# PicoBOB_DLX.net
KiCad netlist of a schematic drawn in Altium Designer
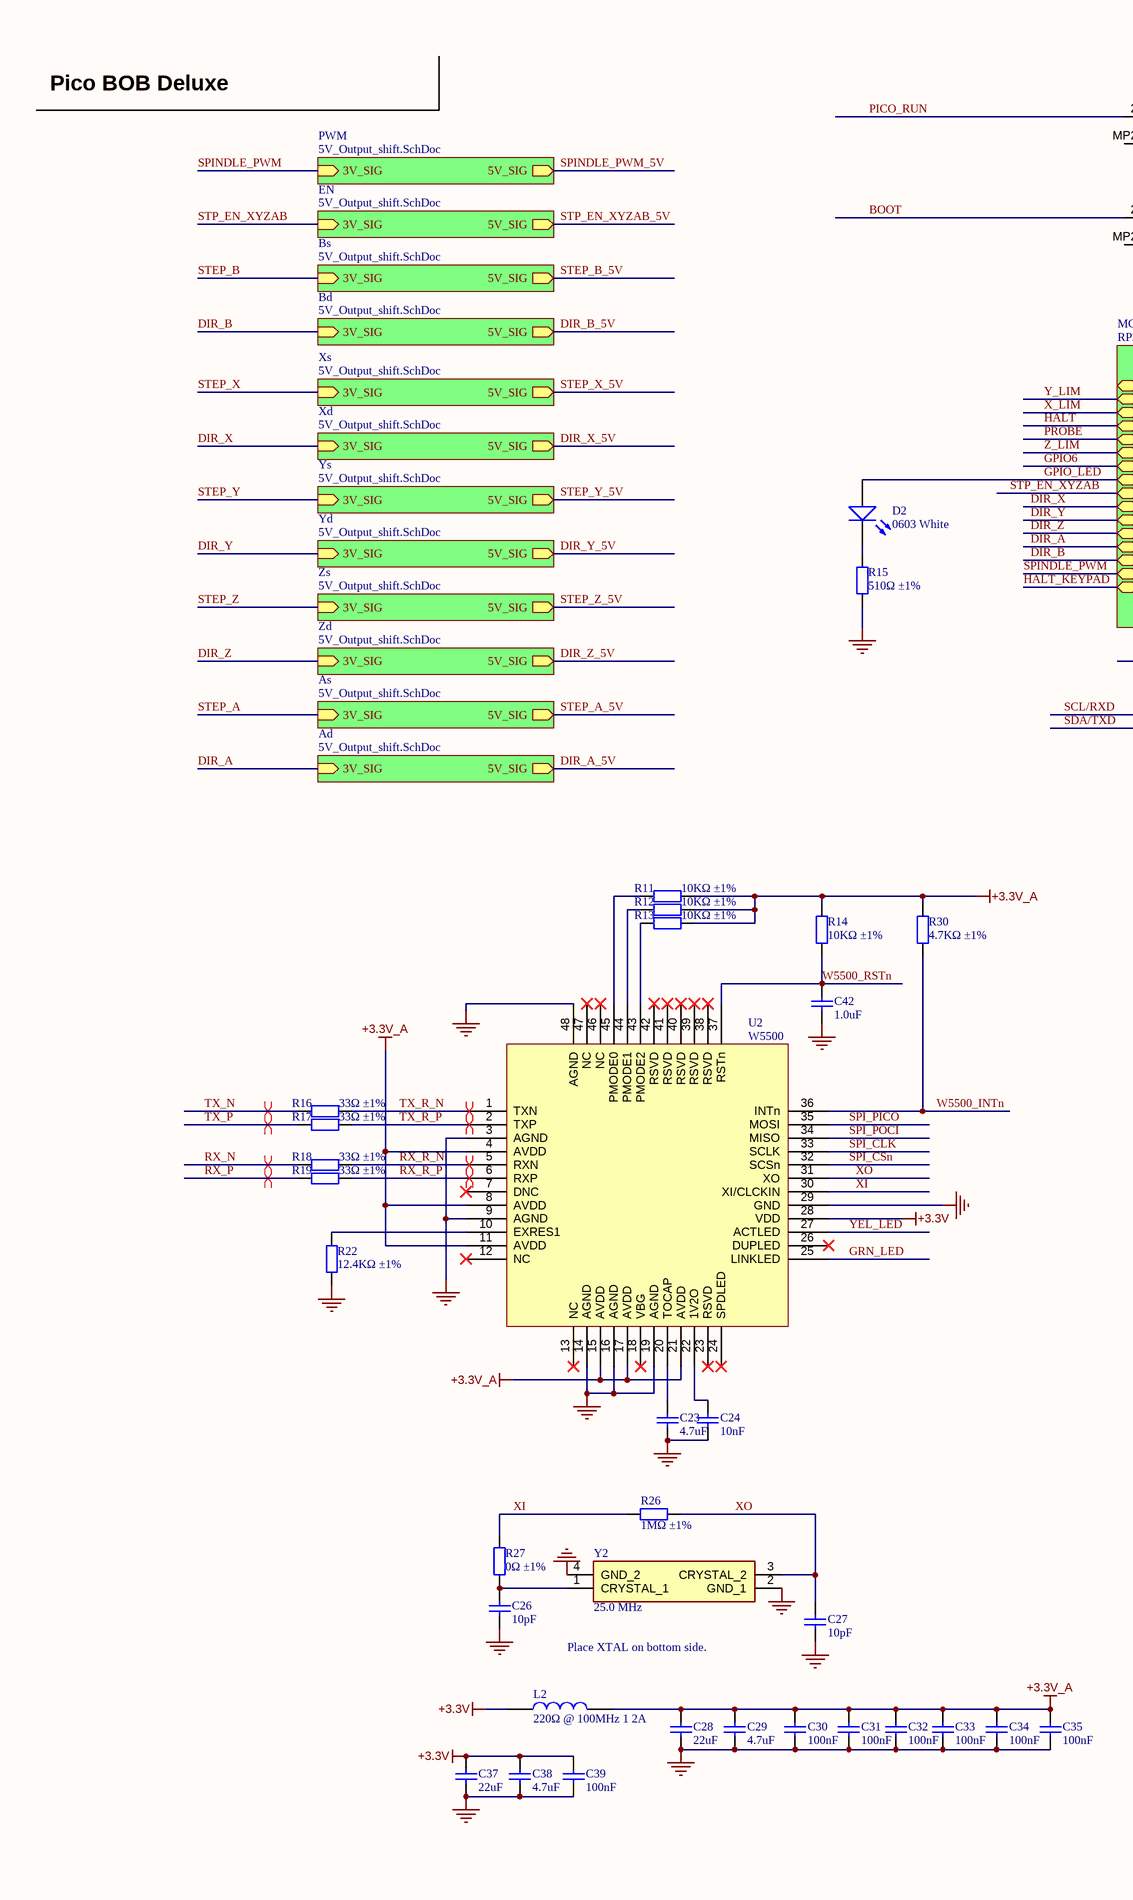
[diagram p0: PicoBOB_DLX.SchDoc, left]
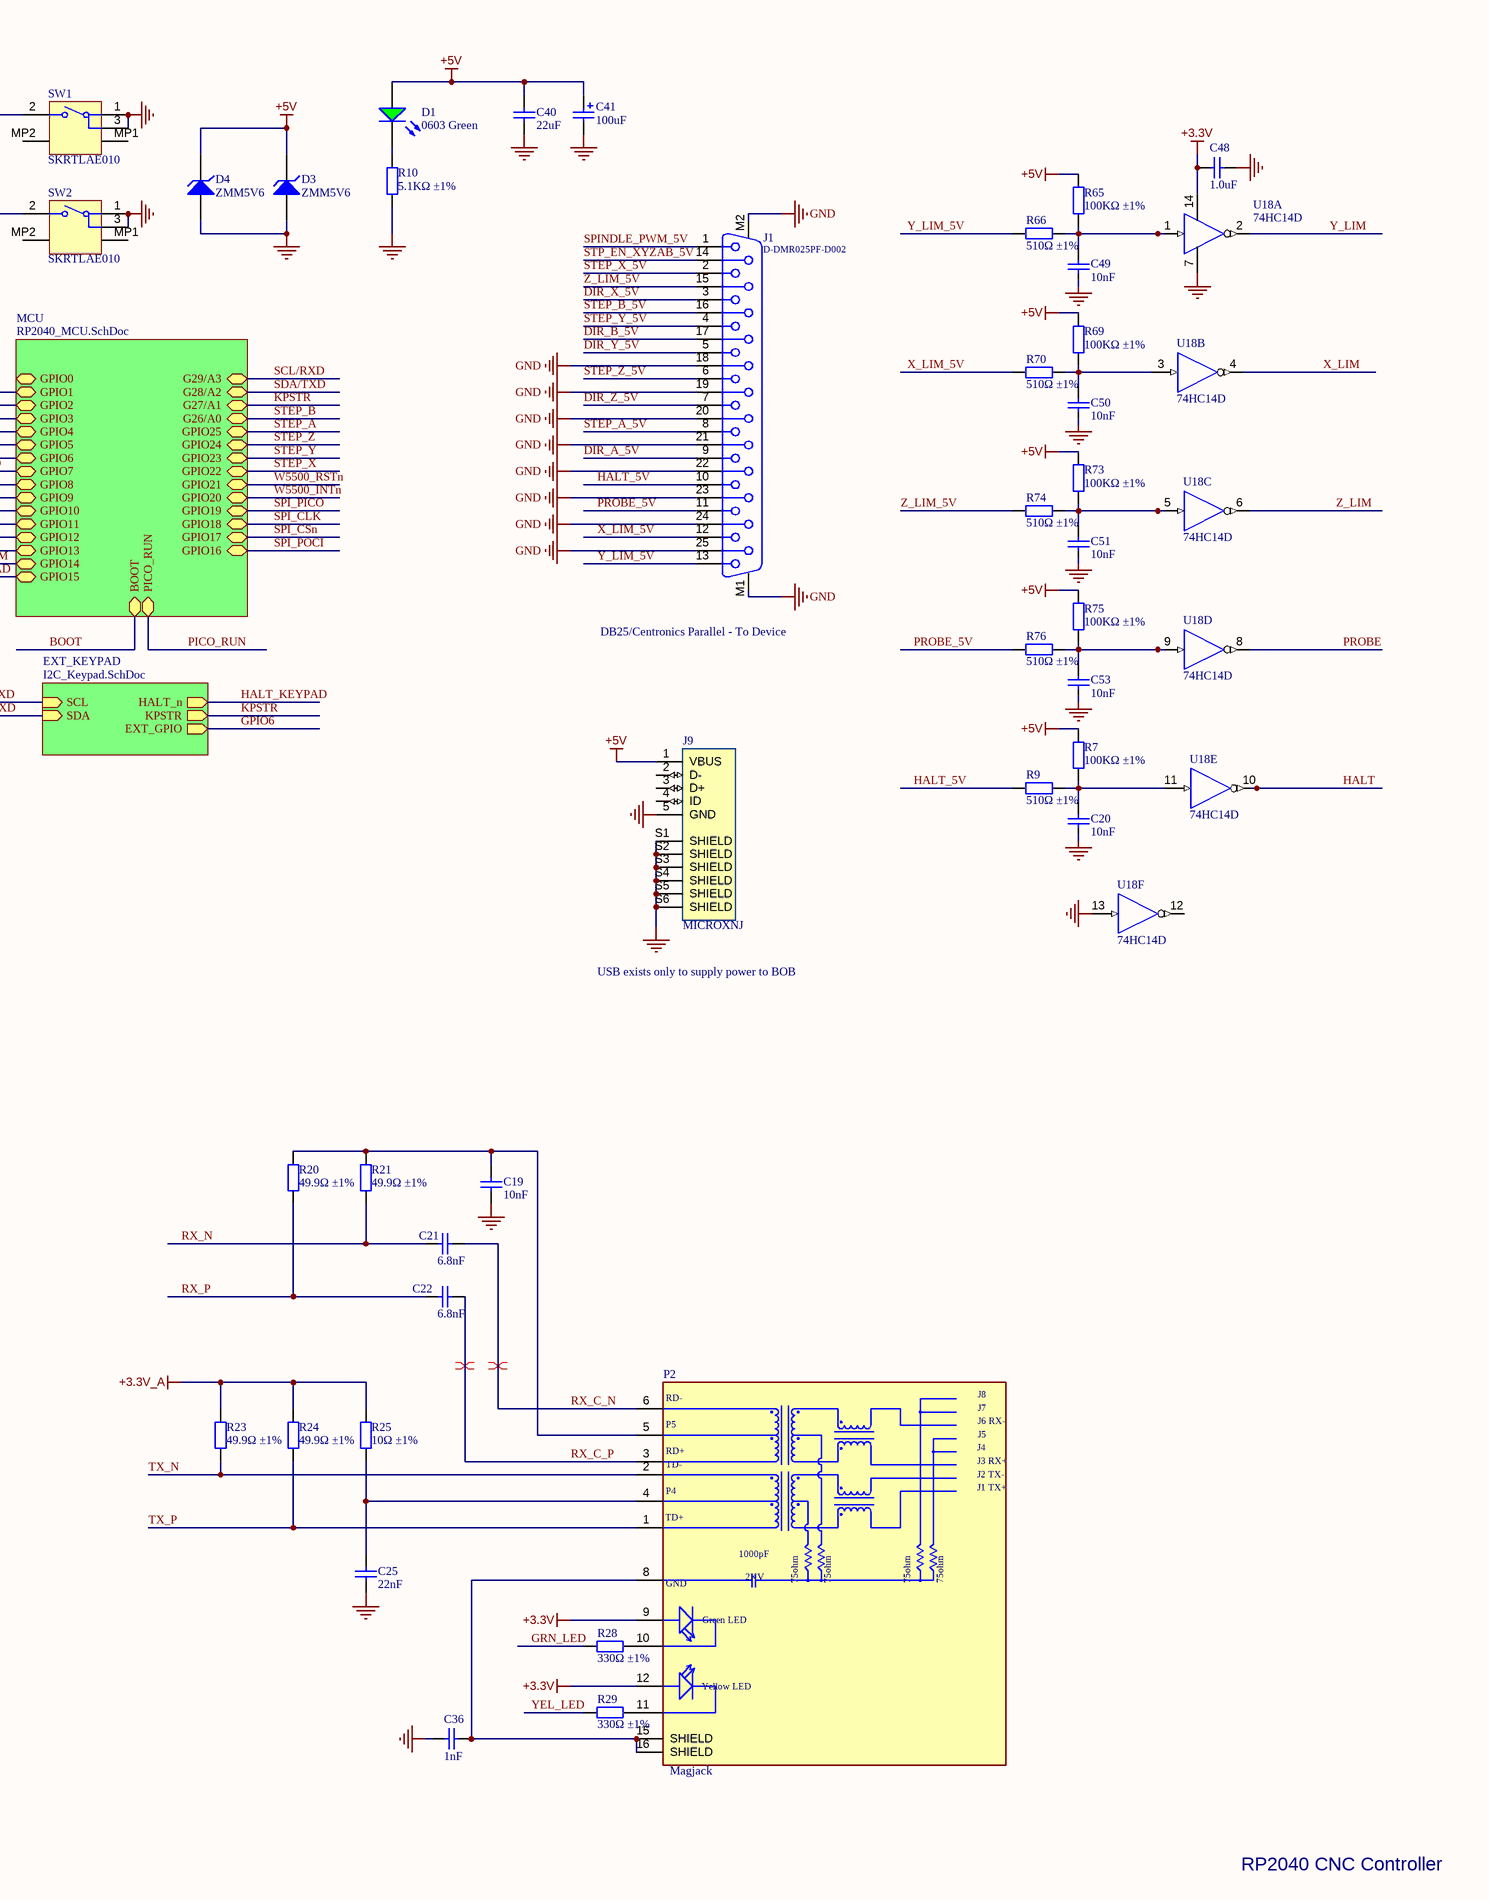
[diagram p1: PicoBOB_DLX.SchDoc, right]

(export (version "E")
  (design (tool "Eeschema 10.0.6"))
  (components
    (comp (ref "C19")
      (value "10nF")
      (footprint "0402_C")
      (description "Chip capacitors")
      (fields
        (field (name "MANUFACTURER") "Samsung Electro-Mechanics")
        (field (name "PARTNUMBER") "CL05B103KB5NNNC")
      )
      (libsource (lib "Cap") (part "0402 10nF (103) 10% 50V"))
    )
    (comp (ref "C20")
      (value "10nF")
      (footprint "0402_C")
      (description "Chip capacitors")
      (fields
        (field (name "MANUFACTURER") "Samsung Electro-Mechanics")
        (field (name "PARTNUMBER") "CL05B103KB5NNNC")
      )
      (libsource (lib "Cap") (part "0402 10nF (103) 10% 50V"))
    )
    (comp (ref "C21")
      (value "6.8nF")
      (footprint "0402_C")
      (description "Chip capacitors")
      (fields
        (field (name "MANUFACTURER") "Guangdong Fenghua Advanced Tech")
        (field (name "PARTNUMBER") "0402B682K500NT")
      )
      (libsource (lib "Cap") (part "0402 6.8nF (682) 10% 50V"))
    )
    (comp (ref "C22")
      (value "6.8nF")
      (footprint "0402_C")
      (description "Chip capacitors")
      (fields
        (field (name "MANUFACTURER") "Guangdong Fenghua Advanced Tech")
        (field (name "PARTNUMBER") "0402B682K500NT")
      )
      (libsource (lib "Cap") (part "0402 6.8nF (682) 10% 50V"))
    )
    (comp (ref "C23")
      (value "4.7uF")
      (footprint "0402_C")
      (description "Chip capacitor")
      (fields
        (field (name "MANUFACTURER") "Samsung Electro-Mechanics")
        (field (name "PARTNUMBER") "CL05A475MP5NRNC")
      )
      (libsource (lib "Cap") (part "0402 4.7uF (475) 20% 10V"))
    )
    (comp (ref "C24")
      (value "10nF")
      (footprint "0402_C")
      (description "Chip capacitors")
      (fields
        (field (name "MANUFACTURER") "Samsung Electro-Mechanics")
        (field (name "PARTNUMBER") "CL05B103KB5NNNC")
      )
      (libsource (lib "Cap") (part "0402 10nF (103) 10% 50V"))
    )
    (comp (ref "C25")
      (value "22nF")
      (footprint "0402_C")
      (description "Chip capacitors")
      (fields
        (field (name "MANUFACTURER") "Guangdong Fenghua Advanced Tech")
        (field (name "PARTNUMBER") "0402B223K500NT")
      )
      (libsource (lib "Cap") (part "0402 22nF (223) 10% 50V"))
    )
    (comp (ref "C26")
      (value "10pF")
      (footprint "0402_C")
      (description "Chip capacitors")
      (fields
        (field (name "MANUFACTURER") "Samsung Electro-Mechanics")
        (field (name "PARTNUMBER") "CL05C100JB5NNNC")
      )
      (libsource (lib "Cap") (part "0402 10pF (100) 5% 50V"))
    )
    (comp (ref "C27")
      (value "10pF")
      (footprint "0402_C")
      (description "Chip capacitors")
      (fields
        (field (name "MANUFACTURER") "Samsung Electro-Mechanics")
        (field (name "PARTNUMBER") "CL05C100JB5NNNC")
      )
      (libsource (lib "Cap") (part "0402 10pF (100) 5% 50V"))
    )
    (comp (ref "C28")
      (value "22uF")
      (footprint "0805_C")
      (description "Chip capacitors")
      (fields
        (field (name "MANUFACTURER") "Samsung Electro-Mechanics")
        (field (name "PARTNUMBER") "CL21A226MAQNNNE")
      )
      (libsource (lib "Cap") (part "0805 22uF (226) 20% 25V"))
    )
    (comp (ref "C29")
      (value "4.7uF")
      (footprint "0603_C")
      (description "Chip capacitors")
      (fields
        (field (name "MANUFACTURER") "Samsung Electro-Mechanics")
        (field (name "PARTNUMBER") "CL10A475KO8NNNC")
      )
      (libsource (lib "Cap") (part "0603 4.7uF (475) 10% 16V"))
    )
    (comp (ref "C30")
      (value "100nF")
      (footprint "0402_C")
      (description "Chip capacitors")
      (fields
        (field (name "MANUFACTURER") "Samsung Electro-Mechanics")
        (field (name "PARTNUMBER") "CL05B104KO5NNNC")
      )
      (libsource (lib "Cap") (part "0402 100nF (104) 10% 16V"))
    )
    (comp (ref "C31")
      (value "100nF")
      (footprint "0402_C")
      (description "Chip capacitors")
      (fields
        (field (name "MANUFACTURER") "Samsung Electro-Mechanics")
        (field (name "PARTNUMBER") "CL05B104KO5NNNC")
      )
      (libsource (lib "Cap") (part "0402 100nF (104) 10% 16V"))
    )
    (comp (ref "C32")
      (value "100nF")
      (footprint "0402_C")
      (description "Chip capacitors")
      (fields
        (field (name "MANUFACTURER") "Samsung Electro-Mechanics")
        (field (name "PARTNUMBER") "CL05B104KO5NNNC")
      )
      (libsource (lib "Cap") (part "0402 100nF (104) 10% 16V"))
    )
    (comp (ref "C33")
      (value "100nF")
      (footprint "0402_C")
      (description "Chip capacitors")
      (fields
        (field (name "MANUFACTURER") "Samsung Electro-Mechanics")
        (field (name "PARTNUMBER") "CL05B104KO5NNNC")
      )
      (libsource (lib "Cap") (part "0402 100nF (104) 10% 16V"))
    )
    (comp (ref "C34")
      (value "100nF")
      (footprint "0402_C")
      (description "Chip capacitors")
      (fields
        (field (name "MANUFACTURER") "Samsung Electro-Mechanics")
        (field (name "PARTNUMBER") "CL05B104KO5NNNC")
      )
      (libsource (lib "Cap") (part "0402 100nF (104) 10% 16V"))
    )
    (comp (ref "C35")
      (value "100nF")
      (footprint "0402_C")
      (description "Chip capacitors")
      (fields
        (field (name "MANUFACTURER") "Samsung Electro-Mechanics")
        (field (name "PARTNUMBER") "CL05B104KO5NNNC")
      )
      (libsource (lib "Cap") (part "0402 100nF (104) 10% 16V"))
    )
    (comp (ref "C36")
      (value "1nF")
      (footprint "1206_C")
      (description "Chip capacitors")
      (fields
        (field (name "MANUFACTURER") "Samsung Electro-Mechanics")
        (field (name "PARTNUMBER") "CL31B102KGFNNNE")
      )
      (libsource (lib "Cap") (part "1206 1nF (102) 10% 500V"))
    )
    (comp (ref "C37")
      (value "22uF")
      (footprint "0805_C")
      (description "Chip capacitors")
      (fields
        (field (name "MANUFACTURER") "Samsung Electro-Mechanics")
        (field (name "PARTNUMBER") "CL21A226MAQNNNE")
      )
      (libsource (lib "Cap") (part "0805 22uF (226) 20% 25V"))
    )
    (comp (ref "C38")
      (value "4.7uF")
      (footprint "0603_C")
      (description "Chip capacitors")
      (fields
        (field (name "MANUFACTURER") "Samsung Electro-Mechanics")
        (field (name "PARTNUMBER") "CL10A475KO8NNNC")
      )
      (libsource (lib "Cap") (part "0603 4.7uF (475) 10% 16V"))
    )
    (comp (ref "C39")
      (value "100nF")
      (footprint "0402_C")
      (description "Chip capacitors")
      (fields
        (field (name "MANUFACTURER") "Samsung Electro-Mechanics")
        (field (name "PARTNUMBER") "CL05B104KO5NNNC")
      )
      (libsource (lib "Cap") (part "0402 100nF (104) 10% 16V"))
    )
    (comp (ref "C40")
      (value "22uF")
      (footprint "0805_C")
      (description "Chip capacitors")
      (fields
        (field (name "MANUFACTURER") "Samsung Electro-Mechanics")
        (field (name "PARTNUMBER") "CL21A226MAQNNNE")
      )
      (libsource (lib "Cap") (part "0805 22uF (226) 20% 25V"))
    )
    (comp (ref "C41")
      (value "100uF")
      (footprint "CASE-B_3528")
      (description "Tantalum capacitor")
      (fields (field (name "MANUFACTURER") "AVX") (field (name "PARTNUMBER") "TAJB107K006RNJ"))
      (libsource (lib "Cap") (part "3528 100uF (107) 10% 6.3V"))
    )
    (comp (ref "C42")
      (value "1.0uF")
      (footprint "0402_C")
      (description "Chip capacitor")
      (fields
        (field (name "MANUFACTURER") "Samsung Electro-Mechanics")
        (field (name "PARTNUMBER") "CL05A105KA5NQNC")
      )
      (libsource (lib "Cap") (part "0402 1.0uF (105) 10% 25V"))
    )
    (comp (ref "C48")
      (value "1.0uF")
      (footprint "0402_C")
      (description "Chip capacitor")
      (fields
        (field (name "MANUFACTURER") "Samsung Electro-Mechanics")
        (field (name "PARTNUMBER") "CL05A105KA5NQNC")
      )
      (libsource (lib "Cap") (part "0402 1.0uF (105) 10% 25V"))
    )
    (comp (ref "C49")
      (value "10nF")
      (footprint "0402_C")
      (description "Chip capacitors")
      (fields
        (field (name "MANUFACTURER") "Samsung Electro-Mechanics")
        (field (name "PARTNUMBER") "CL05B103KB5NNNC")
      )
      (libsource (lib "Cap") (part "0402 10nF (103) 10% 50V"))
    )
    (comp (ref "C50")
      (value "10nF")
      (footprint "0402_C")
      (description "Chip capacitors")
      (fields
        (field (name "MANUFACTURER") "Samsung Electro-Mechanics")
        (field (name "PARTNUMBER") "CL05B103KB5NNNC")
      )
      (libsource (lib "Cap") (part "0402 10nF (103) 10% 50V"))
    )
    (comp (ref "C51")
      (value "10nF")
      (footprint "0402_C")
      (description "Chip capacitors")
      (fields
        (field (name "MANUFACTURER") "Samsung Electro-Mechanics")
        (field (name "PARTNUMBER") "CL05B103KB5NNNC")
      )
      (libsource (lib "Cap") (part "0402 10nF (103) 10% 50V"))
    )
    (comp (ref "C53")
      (value "10nF")
      (footprint "0402_C")
      (description "Chip capacitors")
      (fields
        (field (name "MANUFACTURER") "Samsung Electro-Mechanics")
        (field (name "PARTNUMBER") "CL05B103KB5NNNC")
      )
      (libsource (lib "Cap") (part "0402 10nF (103) 10% 50V"))
    )
    (comp (ref "D1")
      (value "0603 Green")
      (footprint "0603_LED_S1")
      (description "LED")
      (libsource (lib "LED") (part "0603 LED Green"))
    )
    (comp (ref "D2")
      (value "0603 White")
      (footprint "0603_LED_S1")
      (description "LED")
      (libsource (lib "LED") (part "0603 LED White"))
    )
    (comp (ref "D3")
      (value "ZMM5V6")
      (footprint "LL-34")
      (description "500mW - 0.1uA @ 1V 5.6V LL-34 Zener Diodes ROHS")
      (libsource (lib "Zener") (part "LL-34 ZMM5V6"))
    )
    (comp (ref "D4")
      (value "ZMM5V6")
      (footprint "LL-34")
      (description "500mW - 0.1uA @ 1V 5.6V LL-34 Zener Diodes ROHS")
      (libsource (lib "Zener") (part "LL-34 ZMM5V6"))
    )
    (comp (ref "J1")
      (value "D-DMR025PF-D002")
      (footprint "618025231121")
      (description "Through Hole,P=2.77mm D-Sub Connectors ROHS")
      (libsource (lib "Altium Content Vault") (part "WE-CN-2S-2F-D25"))
    )
    (comp (ref "J9")
      (value "MICROXNJ")
      (footprint "SHOUHAN_MICROXNJ")
      (description "Micro USB")
      (fields (field (name "MF") "Shouhan"))
      (libsource (lib "Universal_CNC_Breakout") (part "MICROXNJ"))
    )
    (comp (ref "L2")
      (value "220Ω @ 100MHz 1 2A")
      (footprint "0805_C")
      (description "220Ω @ 100MHz 1 2A 150mΩ 0805 Ferrite Beads ROHS")
      (libsource (lib "FBEAD") (part "0402 220R@100Mhz 0.1A"))
    )
    (comp (ref "P2")
      (value "Magjack")
      (footprint "HANRUN_HR911105A")
      (description "HR911105A Ethernet Interface Arduino Platform Evaluation Expansion Board")
      (fields (field (name "MP") "HR911105A") (field (name "MF") "DFRobot"))
      (libsource (lib "PrintNC_GRBLHAL_Breakout") (part "HR911105A"))
    )
    (comp (ref "R7")
      (value "100KΩ ±1%")
      (footprint "0402_R")
      (description "Chip resistor")
      (fields (field (name "MANUFACTURER") "Uniroyal Elec") (field (name "PARTNUMBER") "0402WGF1003TCE"))
      (libsource (lib "RES") (part "0402 100K (1003) 1%"))
    )
    (comp (ref "R9")
      (value "510Ω ±1%")
      (footprint "0402_R")
      (description "Chip resistor")
      (fields (field (name "MANUFACTURER") "Uniroyal Elec") (field (name "PARTNUMBER") "0402WGF5100TCE"))
      (libsource (lib "RES") (part "0402 510R (5100) 1%"))
    )
    (comp (ref "R10")
      (value "5.1KΩ ±1%")
      (footprint "0402_R")
      (description "Chip resistor")
      (fields (field (name "MANUFACTURER") "Uniroyal Elec") (field (name "PARTNUMBER") "0402WGF5101TCE"))
      (libsource (lib "RES") (part "0402 5.1K (5101) 1%"))
    )
    (comp (ref "R11")
      (value "10KΩ ±1%")
      (footprint "0402_R")
      (description "Chip resistor")
      (fields (field (name "MANUFACTURER") "Uniroyal Elec") (field (name "PARTNUMBER") "0402WGF1002TCE"))
      (libsource (lib "") (part "0402 10K (1002) 1%_1"))
    )
    (comp (ref "R12")
      (value "10KΩ ±1%")
      (footprint "0402_R")
      (description "Chip resistor")
      (fields (field (name "MANUFACTURER") "Uniroyal Elec") (field (name "PARTNUMBER") "0402WGF1002TCE"))
      (libsource (lib "") (part "0402 10K (1002) 1%_1"))
    )
    (comp (ref "R13")
      (value "10KΩ ±1%")
      (footprint "0402_R")
      (description "Chip resistor")
      (fields (field (name "MANUFACTURER") "Uniroyal Elec") (field (name "PARTNUMBER") "0402WGF1002TCE"))
      (libsource (lib "") (part "0402 10K (1002) 1%_1"))
    )
    (comp (ref "R14")
      (value "10KΩ ±1%")
      (footprint "0402_R")
      (description "Chip resistor")
      (fields (field (name "MANUFACTURER") "Uniroyal Elec") (field (name "PARTNUMBER") "0402WGF1002TCE"))
      (libsource (lib "RES") (part "0402 10K (1002) 1%"))
    )
    (comp (ref "R15")
      (value "510Ω ±1%")
      (footprint "0402_R")
      (description "Chip resistor")
      (fields (field (name "MANUFACTURER") "Uniroyal Elec") (field (name "PARTNUMBER") "0402WGF5100TCE"))
      (libsource (lib "") (part "0402 510R (5100) 1%_1"))
    )
    (comp (ref "R16")
      (value "33Ω ±1%")
      (footprint "0402_R")
      (description "Chip resistor")
      (fields (field (name "MANUFACTURER") "Uniroyal Elec") (field (name "PARTNUMBER") "0402WGF330JTCE"))
      (libsource (lib "RES") (part "0402 33R (33R0) 1%"))
    )
    (comp (ref "R17")
      (value "33Ω ±1%")
      (footprint "0402_R")
      (description "Chip resistor")
      (fields (field (name "MANUFACTURER") "Uniroyal Elec") (field (name "PARTNUMBER") "0402WGF330JTCE"))
      (libsource (lib "RES") (part "0402 33R (33R0) 1%"))
    )
    (comp (ref "R18")
      (value "33Ω ±1%")
      (footprint "0402_R")
      (description "Chip resistor")
      (fields (field (name "MANUFACTURER") "Uniroyal Elec") (field (name "PARTNUMBER") "0402WGF330JTCE"))
      (libsource (lib "RES") (part "0402 33R (33R0) 1%"))
    )
    (comp (ref "R19")
      (value "33Ω ±1%")
      (footprint "0402_R")
      (description "Chip resistor")
      (fields (field (name "MANUFACTURER") "Uniroyal Elec") (field (name "PARTNUMBER") "0402WGF330JTCE"))
      (libsource (lib "RES") (part "0402 33R (33R0) 1%"))
    )
    (comp (ref "R20")
      (value "49.9Ω ±1%")
      (footprint "0402_R")
      (description "Chip resistor")
      (fields (field (name "MANUFACTURER") "Uniroyal Elec") (field (name "PARTNUMBER") "0402WGF499JTCE"))
      (libsource (lib "RES") (part "0402 49.9R (49R9) 1%"))
    )
    (comp (ref "R21")
      (value "49.9Ω ±1%")
      (footprint "0402_R")
      (description "Chip resistor")
      (fields (field (name "MANUFACTURER") "Uniroyal Elec") (field (name "PARTNUMBER") "0402WGF499JTCE"))
      (libsource (lib "RES") (part "0402 49.9R (49R9) 1%"))
    )
    (comp (ref "R22")
      (value "12.4KΩ ±1%")
      (footprint "0603_R")
      (description "Chip resistor")
      (fields (field (name "MANUFACTURER") "Uniroyal Elec") (field (name "PARTNUMBER") "0603WAF1242T5E"))
      (libsource (lib "RES") (part "0603 10K (1002) 1%"))
    )
    (comp (ref "R23")
      (value "49.9Ω ±1%")
      (footprint "0402_R")
      (description "Chip resistor")
      (fields (field (name "MANUFACTURER") "Uniroyal Elec") (field (name "PARTNUMBER") "0402WGF499JTCE"))
      (libsource (lib "RES") (part "0402 49.9R (49R9) 1%"))
    )
    (comp (ref "R24")
      (value "49.9Ω ±1%")
      (footprint "0402_R")
      (description "Chip resistor")
      (fields (field (name "MANUFACTURER") "Uniroyal Elec") (field (name "PARTNUMBER") "0402WGF499JTCE"))
      (libsource (lib "RES") (part "0402 49.9R (49R9) 1%"))
    )
    (comp (ref "R25")
      (value "10Ω ±1%")
      (footprint "0402_R")
      (description "Chip resistor")
      (fields (field (name "MANUFACTURER") "Uniroyal Elec") (field (name "PARTNUMBER") "0402WGF100JTCE"))
      (libsource (lib "RES") (part "0402 10R (10R0) 1%"))
    )
    (comp (ref "R26")
      (value "1MΩ ±1%")
      (footprint "0402_R")
      (description "Chip resistor")
      (fields (field (name "MANUFACTURER") "Uniroyal Elec") (field (name "PARTNUMBER") "0402WGF1004TCE"))
      (libsource (lib "RES") (part "0402 1M (1004) 1%"))
    )
    (comp (ref "R27")
      (value "0Ω ±1%")
      (footprint "0402_R")
      (description "Chip resistor")
      (fields (field (name "MANUFACTURER") "Uniroyal Elec") (field (name "PARTNUMBER") "0402WGF0000TCE"))
      (libsource (lib "RES") (part "0402 0R (0R0) 1%"))
    )
    (comp (ref "R28")
      (value "330Ω ±1%")
      (footprint "0402_R")
      (description "Chip resistor")
      (fields (field (name "MANUFACTURER") "Uniroyal Elec") (field (name "PARTNUMBER") "0402WGF3300TCE"))
      (libsource (lib "RES") (part "0402 330R (3300) 1%"))
    )
    (comp (ref "R29")
      (value "330Ω ±1%")
      (footprint "0402_R")
      (description "Chip resistor")
      (fields (field (name "MANUFACTURER") "Uniroyal Elec") (field (name "PARTNUMBER") "0402WGF3300TCE"))
      (libsource (lib "RES") (part "0402 330R (3300) 1%"))
    )
    (comp (ref "R30")
      (value "4.7KΩ ±1%")
      (footprint "0402_R")
      (description "Chip resistor")
      (fields (field (name "MANUFACTURER") "Uniroyal Elec") (field (name "PARTNUMBER") "0402WGF4701TCE"))
      (libsource (lib "RES") (part "0402 4.7K (4701) 1%"))
    )
    (comp (ref "R65")
      (value "100KΩ ±1%")
      (footprint "0402_R")
      (description "Chip resistor")
      (fields (field (name "MANUFACTURER") "Uniroyal Elec") (field (name "PARTNUMBER") "0402WGF1003TCE"))
      (libsource (lib "RES") (part "0402 100K (1003) 1%"))
    )
    (comp (ref "R66")
      (value "510Ω ±1%")
      (footprint "0402_R")
      (description "Chip resistor")
      (fields (field (name "MANUFACTURER") "Uniroyal Elec") (field (name "PARTNUMBER") "0402WGF5100TCE"))
      (libsource (lib "RES") (part "0402 510R (5100) 1%"))
    )
    (comp (ref "R69")
      (value "100KΩ ±1%")
      (footprint "0402_R")
      (description "Chip resistor")
      (fields (field (name "MANUFACTURER") "Uniroyal Elec") (field (name "PARTNUMBER") "0402WGF1003TCE"))
      (libsource (lib "RES") (part "0402 100K (1003) 1%"))
    )
    (comp (ref "R70")
      (value "510Ω ±1%")
      (footprint "0402_R")
      (description "Chip resistor")
      (fields (field (name "MANUFACTURER") "Uniroyal Elec") (field (name "PARTNUMBER") "0402WGF5100TCE"))
      (libsource (lib "RES") (part "0402 510R (5100) 1%"))
    )
    (comp (ref "R73")
      (value "100KΩ ±1%")
      (footprint "0402_R")
      (description "Chip resistor")
      (fields (field (name "MANUFACTURER") "Uniroyal Elec") (field (name "PARTNUMBER") "0402WGF1003TCE"))
      (libsource (lib "RES") (part "0402 100K (1003) 1%"))
    )
    (comp (ref "R74")
      (value "510Ω ±1%")
      (footprint "0402_R")
      (description "Chip resistor")
      (fields (field (name "MANUFACTURER") "Uniroyal Elec") (field (name "PARTNUMBER") "0402WGF5100TCE"))
      (libsource (lib "RES") (part "0402 510R (5100) 1%"))
    )
    (comp (ref "R75")
      (value "100KΩ ±1%")
      (footprint "0402_R")
      (description "Chip resistor")
      (fields (field (name "MANUFACTURER") "Uniroyal Elec") (field (name "PARTNUMBER") "0402WGF1003TCE"))
      (libsource (lib "RES") (part "0402 100K (1003) 1%"))
    )
    (comp (ref "R76")
      (value "510Ω ±1%")
      (footprint "0402_R")
      (description "Chip resistor")
      (fields (field (name "MANUFACTURER") "Uniroyal Elec") (field (name "PARTNUMBER") "0402WGF5100TCE"))
      (libsource (lib "RES") (part "0402 510R (5100) 1%"))
    )
    (comp (ref "SW1")
      (value "SKRTLAE010")
      (footprint "ALPS-SKRTLAE010_V")
      (description "Side Push Type, 250 V, -40 to 90 degC, 3-Pin SMD, RoHS, Tape and Reel")
      (fields (field (name "MANUFACTURER") "ALPS"))
      (libsource (lib "Altium Content Vault") (part "SW_SPST-3_A"))
    )
    (comp (ref "SW2")
      (value "SKRTLAE010")
      (footprint "ALPS-SKRTLAE010_V")
      (description "Side Push Type, 250 V, -40 to 90 degC, 3-Pin SMD, RoHS, Tape and Reel")
      (fields (field (name "MANUFACTURER") "ALPS"))
      (libsource (lib "Altium Content Vault") (part "SW_SPST-3_A"))
    )
    (comp (ref "U2")
      (value "W5500")
      (footprint "LQFP-48_7x7x05P")
      (description "Ethernet Controllers 2.97V ~ 3.63V 10/100 Base-T/TX PHY SPI LQFP-48_7x7x05P Ethernet ICs ROHS")
      (libsource (lib "IC") (part "W5500_[C32843]"))
    )
    (comp (ref "U18")
      (value "74HC14D")
      (footprint "SOIC-14_150mil")
      (description "74系列逻辑芯片")
      (libsource (lib "IC") (part "74HC14D_[C5605]"))
    )
    (comp (ref "Y2")
      (value "25.0 MHz")
      (footprint "SamacSys:YSX321SL")
      (description "Crystal or Oscillator")
      (fields (field (name "MANUFACTURER_PART_NUMBER") "X322525MSB4SI"))
      (libsource (lib "*") (part "YSX321SL"))
    )
  )
  (nets
    (net (code "1") (name "+3.3V") (class "Default")
      (node (ref "C37") (pin "2") (pinfunction "2_2") (pintype "passive"))
      (node (ref "C38") (pin "2") (pinfunction "2_2") (pintype "passive"))
      (node (ref "C39") (pin "2") (pinfunction "2_2") (pintype "passive"))
      (node (ref "C48") (pin "1") (pinfunction "1_1") (pintype "passive"))
      (node (ref "L2") (pin "1") (pinfunction "1_1") (pintype "passive"))
      (node (ref "P2") (pin "12") (pinfunction "YA_12") (pintype "passive"))
      (node (ref "P2") (pin "9") (pinfunction "GA_9") (pintype "passive"))
      (node (ref "U18") (pin "14") (pinfunction "VCC_14") (pintype "power_in"))
      (node (ref "U2") (pin "28") (pinfunction "VDD_28") (pintype "passive"))
    )
    (net (code "2") (name "+3.3V_A") (class "Default")
      (node (ref "C28") (pin "2") (pinfunction "2_2") (pintype "passive"))
      (node (ref "C29") (pin "2") (pinfunction "2_2") (pintype "passive"))
      (node (ref "C30") (pin "2") (pinfunction "2_2") (pintype "passive"))
      (node (ref "C31") (pin "2") (pinfunction "2_2") (pintype "passive"))
      (node (ref "C32") (pin "2") (pinfunction "2_2") (pintype "passive"))
      (node (ref "C33") (pin "2") (pinfunction "2_2") (pintype "passive"))
      (node (ref "C34") (pin "2") (pinfunction "2_2") (pintype "passive"))
      (node (ref "C35") (pin "2") (pinfunction "2_2") (pintype "passive"))
      (node (ref "L2") (pin "2") (pinfunction "2_2") (pintype "passive"))
      (node (ref "R11") (pin "1") (pinfunction "1_1") (pintype "passive"))
      (node (ref "R12") (pin "1") (pinfunction "1_1") (pintype "passive"))
      (node (ref "R13") (pin "1") (pinfunction "1_1") (pintype "passive"))
      (node (ref "R14") (pin "2") (pinfunction "2_2") (pintype "passive"))
      (node (ref "R23") (pin "1") (pinfunction "1_1") (pintype "passive"))
      (node (ref "R24") (pin "1") (pinfunction "1_1") (pintype "passive"))
      (node (ref "R25") (pin "1") (pinfunction "1_1") (pintype "passive"))
      (node (ref "R30") (pin "2") (pinfunction "2_2") (pintype "passive"))
      (node (ref "U2") (pin "11") (pinfunction "AVDD_11") (pintype "passive"))
      (node (ref "U2") (pin "15") (pinfunction "AVDD_15") (pintype "passive"))
      (node (ref "U2") (pin "17") (pinfunction "AVDD_17") (pintype "passive"))
      (node (ref "U2") (pin "21") (pinfunction "AVDD_21") (pintype "passive"))
      (node (ref "U2") (pin "4") (pinfunction "AVDD_4") (pintype "passive"))
      (node (ref "U2") (pin "8") (pinfunction "AVDD_8") (pintype "passive"))
    )
    (net (code "3") (name "+5V") (class "Default")
      (node (ref "C40") (pin "2") (pinfunction "2_2") (pintype "passive"))
      (node (ref "C41") (pin "1") (pinfunction "1_1") (pintype "passive"))
      (node (ref "D1") (pin "A") (pinfunction "A_A") (pintype "passive"))
      (node (ref "D3") (pin "2") (pinfunction "K_2") (pintype "passive"))
      (node (ref "D4") (pin "2") (pinfunction "K_2") (pintype "passive"))
      (node (ref "J9") (pin "1") (pinfunction "VBUS_1") (pintype "power_in"))
      (node (ref "R65") (pin "2") (pinfunction "2_2") (pintype "passive"))
      (node (ref "R69") (pin "2") (pinfunction "2_2") (pintype "passive"))
      (node (ref "R7") (pin "2") (pinfunction "2_2") (pintype "passive"))
      (node (ref "R73") (pin "2") (pinfunction "2_2") (pintype "passive"))
      (node (ref "R75") (pin "2") (pinfunction "2_2") (pintype "passive"))
    )
    (net (code "4") (name "/BOOT") (class "Default")
      (node (ref "SW2") (pin "2") (pinfunction "2_2") (pintype "passive"))
    )
    (net (code "6") (name "/DIR_A_5V") (class "Default")
      (node (ref "J1") (pin "9") (pinfunction "9_9") (pintype "passive"))
    )
    (net (code "8") (name "/DIR_B_5V") (class "Default")
      (node (ref "J1") (pin "17") (pinfunction "17_17") (pintype "passive"))
    )
    (net (code "10") (name "/DIR_X_5V") (class "Default")
      (node (ref "J1") (pin "3") (pinfunction "3_3") (pintype "passive"))
    )
    (net (code "12") (name "/DIR_Y_5V") (class "Default")
      (node (ref "J1") (pin "5") (pinfunction "5_5") (pintype "passive"))
    )
    (net (code "14") (name "/DIR_Z_5V") (class "Default")
      (node (ref "J1") (pin "7") (pinfunction "7_7") (pintype "passive"))
    )
    (net (code "17") (name "/GPIO_LED") (class "Default")
      (node (ref "D2") (pin "A") (pinfunction "A_A") (pintype "passive"))
    )
    (net (code "18") (name "/GRN_LED") (class "Default")
      (node (ref "R28") (pin "1") (pinfunction "1_1") (pintype "passive"))
      (node (ref "U2") (pin "25") (pinfunction "LINKLED_25") (pintype "passive"))
    )
    (net (code "19") (name "/HALT") (class "Default")
      (node (ref "U18") (pin "10") (pinfunction "Y_10") (pintype "output"))
    )
    (net (code "20") (name "/HALT_5V") (class "Default")
      (node (ref "J1") (pin "10") (pinfunction "10_10") (pintype "passive"))
      (node (ref "R9") (pin "1") (pinfunction "1_1") (pintype "passive"))
    )
    (net (code "23") (name "/PICO_RUN") (class "Default")
      (node (ref "SW1") (pin "2") (pinfunction "2_2") (pintype "passive"))
    )
    (net (code "24") (name "/PROBE") (class "Default")
      (node (ref "U18") (pin "8") (pinfunction "Y_8") (pintype "output"))
    )
    (net (code "25") (name "/PROBE_5V") (class "Default")
      (node (ref "J1") (pin "11") (pinfunction "11_11") (pintype "passive"))
      (node (ref "R76") (pin "1") (pinfunction "1_1") (pintype "passive"))
    )
    (net (code "26") (name "/RX_C_N") (class "Default")
      (node (ref "C21") (pin "1") (pinfunction "1_1") (pintype "passive"))
      (node (ref "P2") (pin "6") (pinfunction "RD-_6") (pintype "passive"))
    )
    (net (code "27") (name "/RX_C_P") (class "Default")
      (node (ref "C22") (pin "1") (pinfunction "1_1") (pintype "passive"))
      (node (ref "P2") (pin "3") (pinfunction "RD+_3") (pintype "passive"))
    )
    (net (code "28") (name "/RX_N") (class "Default")
      (node (ref "C21") (pin "2") (pinfunction "2_2") (pintype "passive"))
      (node (ref "R18") (pin "1") (pinfunction "1_1") (pintype "passive"))
      (node (ref "R21") (pin "2") (pinfunction "2_2") (pintype "passive"))
    )
    (net (code "29") (name "/RX_P") (class "Default")
      (node (ref "C22") (pin "2") (pinfunction "2_2") (pintype "passive"))
      (node (ref "R19") (pin "1") (pinfunction "1_1") (pintype "passive"))
      (node (ref "R20") (pin "2") (pinfunction "2_2") (pintype "passive"))
    )
    (net (code "30") (name "/RX_R_N") (class "Default")
      (node (ref "R18") (pin "2") (pinfunction "2_2") (pintype "passive"))
      (node (ref "U2") (pin "5") (pinfunction "RXN_5") (pintype "passive"))
    )
    (net (code "31") (name "/RX_R_P") (class "Default")
      (node (ref "R19") (pin "2") (pinfunction "2_2") (pintype "passive"))
      (node (ref "U2") (pin "6") (pinfunction "RXP_6") (pintype "passive"))
    )
    (net (code "35") (name "/SPINDLE_PWM_5V") (class "Default")
      (node (ref "J1") (pin "1") (pinfunction "1_1") (pintype "passive"))
    )
    (net (code "36") (name "/SPI_CLK") (class "Default")
      (node (ref "U2") (pin "33") (pinfunction "SCLK_33") (pintype "passive"))
    )
    (net (code "37") (name "/SPI_CSn") (class "Default")
      (node (ref "U2") (pin "32") (pinfunction "SCSn_32") (pintype "passive"))
    )
    (net (code "38") (name "/SPI_PICO") (class "Default")
      (node (ref "U2") (pin "35") (pinfunction "MOSI_35") (pintype "passive"))
    )
    (net (code "39") (name "/SPI_POCI") (class "Default")
      (node (ref "U2") (pin "34") (pinfunction "MISO_34") (pintype "passive"))
    )
    (net (code "41") (name "/STEP_A_5V") (class "Default")
      (node (ref "J1") (pin "8") (pinfunction "8_8") (pintype "passive"))
    )
    (net (code "43") (name "/STEP_B_5V") (class "Default")
      (node (ref "J1") (pin "16") (pinfunction "16_16") (pintype "passive"))
    )
    (net (code "45") (name "/STEP_X_5V") (class "Default")
      (node (ref "J1") (pin "2") (pinfunction "2_2") (pintype "passive"))
    )
    (net (code "47") (name "/STEP_Y_5V") (class "Default")
      (node (ref "J1") (pin "4") (pinfunction "4_4") (pintype "passive"))
    )
    (net (code "49") (name "/STEP_Z_5V") (class "Default")
      (node (ref "J1") (pin "6") (pinfunction "6_6") (pintype "passive"))
    )
    (net (code "51") (name "/STP_EN_XYZAB_5V") (class "Default")
      (node (ref "J1") (pin "14") (pinfunction "14_14") (pintype "passive"))
    )
    (net (code "52") (name "/TX_N") (class "Default")
      (node (ref "P2") (pin "2") (pinfunction "TD-_2") (pintype "passive"))
      (node (ref "R16") (pin "1") (pinfunction "1_1") (pintype "passive"))
      (node (ref "R23") (pin "2") (pinfunction "2_2") (pintype "passive"))
    )
    (net (code "53") (name "/TX_P") (class "Default")
      (node (ref "P2") (pin "1") (pinfunction "TD+_1") (pintype "passive"))
      (node (ref "R17") (pin "1") (pinfunction "1_1") (pintype "passive"))
      (node (ref "R24") (pin "2") (pinfunction "2_2") (pintype "passive"))
    )
    (net (code "54") (name "/TX_R_N") (class "Default")
      (node (ref "R16") (pin "2") (pinfunction "2_2") (pintype "passive"))
      (node (ref "U2") (pin "1") (pinfunction "TXN_1") (pintype "passive"))
    )
    (net (code "55") (name "/TX_R_P") (class "Default")
      (node (ref "R17") (pin "2") (pinfunction "2_2") (pintype "passive"))
      (node (ref "U2") (pin "2") (pinfunction "TXP_2") (pintype "passive"))
    )
    (net (code "56") (name "/W5500_INTn") (class "Default")
      (node (ref "R30") (pin "1") (pinfunction "1_1") (pintype "passive"))
      (node (ref "U2") (pin "36") (pinfunction "INTn_36") (pintype "passive"))
    )
    (net (code "57") (name "/W5500_RSTn") (class "Default")
      (node (ref "C42") (pin "2") (pinfunction "2_2") (pintype "passive"))
      (node (ref "R14") (pin "1") (pinfunction "1_1") (pintype "passive"))
      (node (ref "U2") (pin "37") (pinfunction "RSTn_37") (pintype "passive"))
    )
    (net (code "58") (name "/XI") (class "Default")
      (node (ref "R26") (pin "1") (pinfunction "1_1") (pintype "passive"))
      (node (ref "R27") (pin "1") (pinfunction "1_1") (pintype "passive"))
      (node (ref "U2") (pin "30") (pinfunction "XI/CLCKIN_30") (pintype "passive"))
    )
    (net (code "59") (name "/XO") (class "Default")
      (node (ref "C27") (pin "2") (pinfunction "2_2") (pintype "passive"))
      (node (ref "R26") (pin "2") (pinfunction "2_2") (pintype "passive"))
      (node (ref "U2") (pin "31") (pinfunction "XO_31") (pintype "passive"))
      (node (ref "Y2") (pin "3") (pinfunction "CRYSTAL_2_3") (pintype "passive"))
    )
    (net (code "60") (name "/X_LIM") (class "Default")
      (node (ref "U18") (pin "4") (pinfunction "Y_4") (pintype "output"))
    )
    (net (code "61") (name "/X_LIM_5V") (class "Default")
      (node (ref "J1") (pin "12") (pinfunction "12_12") (pintype "passive"))
      (node (ref "R70") (pin "1") (pinfunction "1_1") (pintype "passive"))
    )
    (net (code "62") (name "/YEL_LED") (class "Default")
      (node (ref "R29") (pin "1") (pinfunction "1_1") (pintype "passive"))
      (node (ref "U2") (pin "27") (pinfunction "ACTLED_27") (pintype "passive"))
    )
    (net (code "63") (name "/Y_LIM") (class "Default")
      (node (ref "U18") (pin "2") (pinfunction "Y_2") (pintype "output"))
    )
    (net (code "64") (name "/Y_LIM_5V") (class "Default")
      (node (ref "J1") (pin "13") (pinfunction "13_13") (pintype "passive"))
      (node (ref "R66") (pin "1") (pinfunction "1_1") (pintype "passive"))
    )
    (net (code "65") (name "/Z_LIM") (class "Default")
      (node (ref "U18") (pin "6") (pinfunction "Y_6") (pintype "output"))
    )
    (net (code "66") (name "/Z_LIM_5V") (class "Default")
      (node (ref "J1") (pin "15") (pinfunction "15_15") (pintype "passive"))
      (node (ref "R74") (pin "1") (pinfunction "1_1") (pintype "passive"))
    )
    (net (code "67") (name "GND") (class "Default")
      (node (ref "C19") (pin "1") (pinfunction "1_1") (pintype "passive"))
      (node (ref "C20") (pin "1") (pinfunction "1_1") (pintype "passive"))
      (node (ref "C23") (pin "1") (pinfunction "1_1") (pintype "passive"))
      (node (ref "C24") (pin "1") (pinfunction "1_1") (pintype "passive"))
      (node (ref "C25") (pin "1") (pinfunction "1_1") (pintype "passive"))
      (node (ref "C26") (pin "1") (pinfunction "1_1") (pintype "passive"))
      (node (ref "C27") (pin "1") (pinfunction "1_1") (pintype "passive"))
      (node (ref "C28") (pin "1") (pinfunction "1_1") (pintype "passive"))
      (node (ref "C29") (pin "1") (pinfunction "1_1") (pintype "passive"))
      (node (ref "C30") (pin "1") (pinfunction "1_1") (pintype "passive"))
      (node (ref "C31") (pin "1") (pinfunction "1_1") (pintype "passive"))
      (node (ref "C32") (pin "1") (pinfunction "1_1") (pintype "passive"))
      (node (ref "C33") (pin "1") (pinfunction "1_1") (pintype "passive"))
      (node (ref "C34") (pin "1") (pinfunction "1_1") (pintype "passive"))
      (node (ref "C35") (pin "1") (pinfunction "1_1") (pintype "passive"))
      (node (ref "C36") (pin "1") (pinfunction "1_1") (pintype "passive"))
      (node (ref "C37") (pin "1") (pinfunction "1_1") (pintype "passive"))
      (node (ref "C38") (pin "1") (pinfunction "1_1") (pintype "passive"))
      (node (ref "C39") (pin "1") (pinfunction "1_1") (pintype "passive"))
      (node (ref "C40") (pin "1") (pinfunction "1_1") (pintype "passive"))
      (node (ref "C41") (pin "2") (pinfunction "2_2") (pintype "passive"))
      (node (ref "C42") (pin "1") (pinfunction "1_1") (pintype "passive"))
      (node (ref "C48") (pin "2") (pinfunction "2_2") (pintype "passive"))
      (node (ref "C49") (pin "1") (pinfunction "1_1") (pintype "passive"))
      (node (ref "C50") (pin "1") (pinfunction "1_1") (pintype "passive"))
      (node (ref "C51") (pin "1") (pinfunction "1_1") (pintype "passive"))
      (node (ref "C53") (pin "1") (pinfunction "1_1") (pintype "passive"))
      (node (ref "D3") (pin "1") (pinfunction "A_1") (pintype "passive"))
      (node (ref "D4") (pin "1") (pinfunction "A_1") (pintype "passive"))
      (node (ref "J1") (pin "18") (pinfunction "18_18") (pintype "passive"))
      (node (ref "J1") (pin "19") (pinfunction "19_19") (pintype "passive"))
      (node (ref "J1") (pin "20") (pinfunction "20_20") (pintype "passive"))
      (node (ref "J1") (pin "21") (pinfunction "21_21") (pintype "passive"))
      (node (ref "J1") (pin "22") (pinfunction "22_22") (pintype "passive"))
      (node (ref "J1") (pin "23") (pinfunction "23_23") (pintype "passive"))
      (node (ref "J1") (pin "24") (pinfunction "24_24") (pintype "passive"))
      (node (ref "J1") (pin "25") (pinfunction "25_25") (pintype "passive"))
      (node (ref "J1") (pin "M1") (pinfunction "M1_M1") (pintype "passive"))
      (node (ref "J1") (pin "M2") (pinfunction "M2_M2") (pintype "passive"))
      (node (ref "J9") (pin "5") (pinfunction "GND_5") (pintype "power_in"))
      (node (ref "J9") (pin "S1") (pinfunction "SHIELD_S1") (pintype "passive"))
      (node (ref "J9") (pin "S2") (pinfunction "SHIELD_S2") (pintype "passive"))
      (node (ref "J9") (pin "S3") (pinfunction "SHIELD_S3") (pintype "passive"))
      (node (ref "J9") (pin "S4") (pinfunction "SHIELD_S4") (pintype "passive"))
      (node (ref "J9") (pin "S5") (pinfunction "SHIELD_S5") (pintype "passive"))
      (node (ref "J9") (pin "S6") (pinfunction "SHIELD_S6") (pintype "passive"))
      (node (ref "R10") (pin "2") (pinfunction "2_2") (pintype "passive"))
      (node (ref "R15") (pin "1") (pinfunction "1_1") (pintype "passive"))
      (node (ref "R22") (pin "1") (pinfunction "1_1") (pintype "passive"))
      (node (ref "SW1") (pin "1") (pinfunction "1_1") (pintype "passive"))
      (node (ref "SW1") (pin "3") (pinfunction "3_3") (pintype "passive"))
      (node (ref "SW2") (pin "1") (pinfunction "1_1") (pintype "passive"))
      (node (ref "SW2") (pin "3") (pinfunction "3_3") (pintype "passive"))
      (node (ref "U18") (pin "13") (pinfunction "A_13") (pintype "input"))
      (node (ref "U18") (pin "7") (pinfunction "GND_7") (pintype "power_in"))
      (node (ref "U2") (pin "14") (pinfunction "AGND_14") (pintype "passive"))
      (node (ref "U2") (pin "16") (pinfunction "AGND_16") (pintype "passive"))
      (node (ref "U2") (pin "19") (pinfunction "AGND_19") (pintype "passive"))
      (node (ref "U2") (pin "29") (pinfunction "GND_29") (pintype "passive"))
      (node (ref "U2") (pin "3") (pinfunction "AGND_3") (pintype "passive"))
      (node (ref "U2") (pin "48") (pinfunction "AGND_48") (pintype "passive"))
      (node (ref "U2") (pin "9") (pinfunction "AGND_9") (pintype "passive"))
      (node (ref "Y2") (pin "2") (pinfunction "GND_1_2") (pintype "passive"))
      (node (ref "Y2") (pin "4") (pinfunction "GND_2_4") (pintype "passive"))
    )
    (net (code "68") (name "Net-(D1-PadK)") (class "Default")
      (node (ref "D1") (pin "K") (pinfunction "K_K") (pintype "passive"))
      (node (ref "R10") (pin "1") (pinfunction "1_1") (pintype "passive"))
    )
    (net (code "69") (name "Net-(D2-PadK)") (class "Default")
      (node (ref "D2") (pin "K") (pinfunction "K_K") (pintype "passive"))
      (node (ref "R15") (pin "2") (pinfunction "2_2") (pintype "passive"))
    )
    (net (code "70") (name "Net-(P2-GC)") (class "Default")
      (node (ref "P2") (pin "10") (pinfunction "GC_10") (pintype "passive"))
      (node (ref "R28") (pin "2") (pinfunction "2_2") (pintype "passive"))
    )
    (net (code "71") (name "Net-(P2-GND)") (class "Default")
      (node (ref "C36") (pin "2") (pinfunction "2_2") (pintype "passive"))
      (node (ref "P2") (pin "15") (pinfunction "SHIELD_15") (pintype "passive"))
      (node (ref "P2") (pin "16") (pinfunction "SHIELD_16") (pintype "passive"))
      (node (ref "P2") (pin "8") (pinfunction "GND_8") (pintype "power_in"))
    )
    (net (code "72") (name "Net-(P2-P4)") (class "Default")
      (node (ref "C25") (pin "2") (pinfunction "2_2") (pintype "passive"))
      (node (ref "P2") (pin "4") (pinfunction "P4_4") (pintype "passive"))
      (node (ref "R25") (pin "2") (pinfunction "2_2") (pintype "passive"))
    )
    (net (code "73") (name "Net-(P2-P5)") (class "Default")
      (node (ref "C19") (pin "2") (pinfunction "2_2") (pintype "passive"))
      (node (ref "P2") (pin "5") (pinfunction "P5_5") (pintype "passive"))
      (node (ref "R20") (pin "1") (pinfunction "1_1") (pintype "passive"))
      (node (ref "R21") (pin "1") (pinfunction "1_1") (pintype "passive"))
    )
    (net (code "74") (name "Net-(P2-YC)") (class "Default")
      (node (ref "P2") (pin "11") (pinfunction "YC_11") (pintype "passive"))
      (node (ref "R29") (pin "2") (pinfunction "2_2") (pintype "passive"))
    )
    (net (code "75") (name "Net-(U2-1V2O)") (class "Default")
      (node (ref "C24") (pin "2") (pinfunction "2_2") (pintype "passive"))
      (node (ref "U2") (pin "22") (pinfunction "1V2O_22") (pintype "passive"))
    )
    (net (code "76") (name "Net-(U2-EXRES1)") (class "Default")
      (node (ref "R22") (pin "2") (pinfunction "2_2") (pintype "passive"))
      (node (ref "U2") (pin "10") (pinfunction "EXRES1_10") (pintype "passive"))
    )
    (net (code "77") (name "Net-(U2-PMODE0)") (class "Default")
      (node (ref "R11") (pin "2") (pinfunction "2_2") (pintype "passive"))
      (node (ref "U2") (pin "45") (pinfunction "PMODE0_45") (pintype "passive"))
    )
    (net (code "78") (name "Net-(U2-PMODE1)") (class "Default")
      (node (ref "R12") (pin "2") (pinfunction "2_2") (pintype "passive"))
      (node (ref "U2") (pin "44") (pinfunction "PMODE1_44") (pintype "passive"))
    )
    (net (code "79") (name "Net-(U2-PMODE2)") (class "Default")
      (node (ref "R13") (pin "2") (pinfunction "2_2") (pintype "passive"))
      (node (ref "U2") (pin "43") (pinfunction "PMODE2_43") (pintype "passive"))
    )
    (net (code "80") (name "Net-(U2-TOCAP)") (class "Default")
      (node (ref "C23") (pin "2") (pinfunction "2_2") (pintype "passive"))
      (node (ref "U2") (pin "20") (pinfunction "TOCAP_20") (pintype "passive"))
    )
    (net (code "81") (name "Net-(U18A-A)") (class "Default")
      (node (ref "C49") (pin "2") (pinfunction "2_2") (pintype "passive"))
      (node (ref "R65") (pin "1") (pinfunction "1_1") (pintype "passive"))
      (node (ref "R66") (pin "2") (pinfunction "2_2") (pintype "passive"))
      (node (ref "U18") (pin "1") (pinfunction "A_1") (pintype "input"))
    )
    (net (code "82") (name "Net-(U18B-A)") (class "Default")
      (node (ref "C50") (pin "2") (pinfunction "2_2") (pintype "passive"))
      (node (ref "R69") (pin "1") (pinfunction "1_1") (pintype "passive"))
      (node (ref "R70") (pin "2") (pinfunction "2_2") (pintype "passive"))
      (node (ref "U18") (pin "3") (pinfunction "A_3") (pintype "input"))
    )
    (net (code "83") (name "Net-(U18C-A)") (class "Default")
      (node (ref "C51") (pin "2") (pinfunction "2_2") (pintype "passive"))
      (node (ref "R73") (pin "1") (pinfunction "1_1") (pintype "passive"))
      (node (ref "R74") (pin "2") (pinfunction "2_2") (pintype "passive"))
      (node (ref "U18") (pin "5") (pinfunction "A_5") (pintype "input"))
    )
    (net (code "84") (name "Net-(U18D-A)") (class "Default")
      (node (ref "C53") (pin "2") (pinfunction "2_2") (pintype "passive"))
      (node (ref "R75") (pin "1") (pinfunction "1_1") (pintype "passive"))
      (node (ref "R76") (pin "2") (pinfunction "2_2") (pintype "passive"))
      (node (ref "U18") (pin "9") (pinfunction "A_9") (pintype "input"))
    )
    (net (code "85") (name "Net-(U18E-A)") (class "Default")
      (node (ref "C20") (pin "2") (pinfunction "2_2") (pintype "passive"))
      (node (ref "R7") (pin "1") (pinfunction "1_1") (pintype "passive"))
      (node (ref "R9") (pin "2") (pinfunction "2_2") (pintype "passive"))
      (node (ref "U18") (pin "11") (pinfunction "A_11") (pintype "input"))
    )
    (net (code "86") (name "Net-(Y2-CRYSTAL_1)") (class "Default")
      (node (ref "C26") (pin "2") (pinfunction "2_2") (pintype "passive"))
      (node (ref "R27") (pin "2") (pinfunction "2_2") (pintype "passive"))
      (node (ref "Y2") (pin "1") (pinfunction "CRYSTAL_1_1") (pintype "passive"))
    )
    (net (code "87") (name "VDD") (class "Default")
      (node (ref "U18") (pin "14") (pinfunction "VDD_14") (pintype "power_in"))
    )
    (net (code "88") (name "unconnected-(J9-D+-Pad3)") (class "Default")
      (node (ref "J9") (pin "3") (pinfunction "D+_3") (pintype "bidirectional"))
    )
    (net (code "89") (name "unconnected-(J9-D--Pad2)") (class "Default")
      (node (ref "J9") (pin "2") (pinfunction "D-_2") (pintype "bidirectional"))
    )
    (net (code "90") (name "unconnected-(J9-ID-Pad4)") (class "Default")
      (node (ref "J9") (pin "4") (pinfunction "ID_4") (pintype "bidirectional"))
    )
    (net (code "91") (name "unconnected-(SW1-PadMP1)") (class "Default")
      (node (ref "SW1") (pin "MP1") (pinfunction "MP1_MP1") (pintype "passive"))
    )
    (net (code "92") (name "unconnected-(SW1-PadMP2)") (class "Default")
      (node (ref "SW1") (pin "MP2") (pinfunction "MP2_MP2") (pintype "passive"))
    )
    (net (code "93") (name "unconnected-(SW2-PadMP1)") (class "Default")
      (node (ref "SW2") (pin "MP1") (pinfunction "MP1_MP1") (pintype "passive"))
    )
    (net (code "94") (name "unconnected-(SW2-PadMP2)") (class "Default")
      (node (ref "SW2") (pin "MP2") (pinfunction "MP2_MP2") (pintype "passive"))
    )
    (net (code "95") (name "unconnected-(U2-DNC-Pad7)") (class "Default")
      (node (ref "U2") (pin "7") (pinfunction "DNC_7") (pintype "passive+no_connect"))
    )
    (net (code "96") (name "unconnected-(U2-DUPLED-Pad26)") (class "Default")
      (node (ref "U2") (pin "26") (pinfunction "DUPLED_26") (pintype "passive+no_connect"))
    )
    (net (code "97") (name "unconnected-(U2-NC-Pad12)") (class "Default")
      (node (ref "U2") (pin "12") (pinfunction "NC_12") (pintype "passive+no_connect"))
    )
    (net (code "98") (name "unconnected-(U2-NC-Pad13)") (class "Default")
      (node (ref "U2") (pin "13") (pinfunction "NC_13") (pintype "passive+no_connect"))
    )
    (net (code "99") (name "unconnected-(U2-NC-Pad46)") (class "Default")
      (node (ref "U2") (pin "46") (pinfunction "NC_46") (pintype "passive+no_connect"))
    )
    (net (code "100") (name "unconnected-(U2-NC-Pad47)") (class "Default")
      (node (ref "U2") (pin "47") (pinfunction "NC_47") (pintype "passive+no_connect"))
    )
    (net (code "101") (name "unconnected-(U2-RSVD-Pad23)") (class "Default")
      (node (ref "U2") (pin "23") (pinfunction "RSVD_23") (pintype "passive+no_connect"))
    )
    (net (code "102") (name "unconnected-(U2-RSVD-Pad38)") (class "Default")
      (node (ref "U2") (pin "38") (pinfunction "RSVD_38") (pintype "passive+no_connect"))
    )
    (net (code "103") (name "unconnected-(U2-RSVD-Pad39)") (class "Default")
      (node (ref "U2") (pin "39") (pinfunction "RSVD_39") (pintype "passive+no_connect"))
    )
    (net (code "104") (name "unconnected-(U2-RSVD-Pad40)") (class "Default")
      (node (ref "U2") (pin "40") (pinfunction "RSVD_40") (pintype "passive+no_connect"))
    )
    (net (code "105") (name "unconnected-(U2-RSVD-Pad41)") (class "Default")
      (node (ref "U2") (pin "41") (pinfunction "RSVD_41") (pintype "passive+no_connect"))
    )
    (net (code "106") (name "unconnected-(U2-RSVD-Pad42)") (class "Default")
      (node (ref "U2") (pin "42") (pinfunction "RSVD_42") (pintype "passive+no_connect"))
    )
    (net (code "107") (name "unconnected-(U2-SPDLED-Pad24)") (class "Default")
      (node (ref "U2") (pin "24") (pinfunction "SPDLED_24") (pintype "passive+no_connect"))
    )
    (net (code "108") (name "unconnected-(U2-VBG-Pad18)") (class "Default")
      (node (ref "U2") (pin "18") (pinfunction "VBG_18") (pintype "passive+no_connect"))
    )
    (net (code "109") (name "unconnected-(U18F-Y-Pad12)") (class "Default")
      (node (ref "U18") (pin "12") (pinfunction "Y_12") (pintype "output"))
    )
  )
)
